# Four_Channel_Relay_Driver.net
KiCad netlist of a schematic drawn in EAGLE
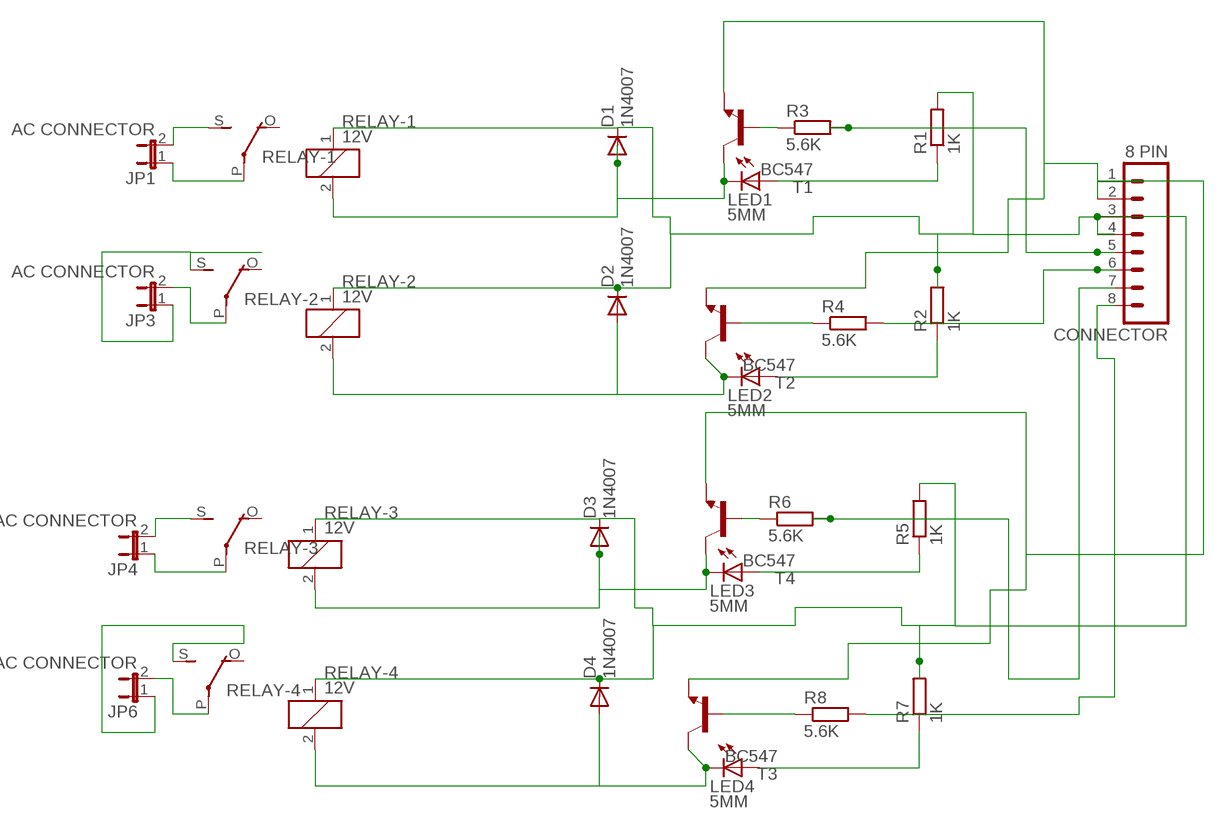
[diagram p0: schematic, sheet 1]

(export (version "E")
  (design (tool "Eeschema 10.0.6"))
  (components
    (comp (ref "CONNECTOR")
      (value "8 PIN")
      (footprint "eagle-import:08P")
      (libsource (lib "eagle-import") (part "M08"))
    )
    (comp (ref "D1")
      (value "1N4007")
      (footprint "eagle-import:DO41-10")
      (libsource (lib "eagle-import") (part "1N4004"))
    )
    (comp (ref "D2")
      (value "1N4007")
      (footprint "eagle-import:DO41-10")
      (libsource (lib "eagle-import") (part "1N4004"))
    )
    (comp (ref "D3")
      (value "1N4007")
      (footprint "eagle-import:DO41-10")
      (libsource (lib "eagle-import") (part "1N4004"))
    )
    (comp (ref "D4")
      (value "1N4007")
      (footprint "eagle-import:DO41-10")
      (libsource (lib "eagle-import") (part "1N4004"))
    )
    (comp (ref "JP1")
      (value "AC CONNECTOR")
      (footprint "eagle-import:JP1")
      (libsource (lib "eagle-import") (part "JP1E"))
    )
    (comp (ref "JP3")
      (value "AC CONNECTOR")
      (footprint "eagle-import:JP1")
      (libsource (lib "eagle-import") (part "JP1E"))
    )
    (comp (ref "JP4")
      (value "AC CONNECTOR")
      (footprint "eagle-import:JP1")
      (libsource (lib "eagle-import") (part "JP1E"))
    )
    (comp (ref "JP6")
      (value "AC CONNECTOR")
      (footprint "eagle-import:JP1")
      (libsource (lib "eagle-import") (part "JP1E"))
    )
    (comp (ref "LED1")
      (value "5MM")
      (footprint "eagle-import:LED5MM")
      (libsource (lib "eagle-import") (part "LED5MM"))
    )
    (comp (ref "LED2")
      (value "5MM")
      (footprint "eagle-import:LED5MM")
      (libsource (lib "eagle-import") (part "LED5MM"))
    )
    (comp (ref "LED3")
      (value "5MM")
      (footprint "eagle-import:LED5MM")
      (libsource (lib "eagle-import") (part "LED5MM"))
    )
    (comp (ref "LED4")
      (value "5MM")
      (footprint "eagle-import:LED5MM")
      (libsource (lib "eagle-import") (part "LED5MM"))
    )
    (comp (ref "R1")
      (value "1K")
      (footprint "eagle-import:0204_7")
      (libsource (lib "eagle-import") (part "R-EU_0204/7"))
    )
    (comp (ref "R2")
      (value "1K")
      (footprint "eagle-import:0204_7")
      (libsource (lib "eagle-import") (part "R-EU_0204/7"))
    )
    (comp (ref "R3")
      (value "5.6K")
      (footprint "eagle-import:0204_7")
      (libsource (lib "eagle-import") (part "R-EU_0204/7"))
    )
    (comp (ref "R4")
      (value "5.6K")
      (footprint "eagle-import:0204_7")
      (libsource (lib "eagle-import") (part "R-EU_0204/7"))
    )
    (comp (ref "R5")
      (value "1K")
      (footprint "eagle-import:0204_7")
      (libsource (lib "eagle-import") (part "R-EU_0204/7"))
    )
    (comp (ref "R6")
      (value "5.6K")
      (footprint "eagle-import:0204_7")
      (libsource (lib "eagle-import") (part "R-EU_0204/7"))
    )
    (comp (ref "R7")
      (value "1K")
      (footprint "eagle-import:0204_7")
      (libsource (lib "eagle-import") (part "R-EU_0204/7"))
    )
    (comp (ref "R8")
      (value "5.6K")
      (footprint "eagle-import:0204_7")
      (libsource (lib "eagle-import") (part "R-EU_0204/7"))
    )
    (comp (ref "RELAY-1")
      (value "12V")
      (footprint "eagle-import:G5LE")
      (libsource (lib "eagle-import") (part "G5L"))
    )
    (comp (ref "RELAY-2")
      (value "12V")
      (footprint "eagle-import:G5LE")
      (libsource (lib "eagle-import") (part "G5L"))
    )
    (comp (ref "RELAY-3")
      (value "12V")
      (footprint "eagle-import:G5LE")
      (libsource (lib "eagle-import") (part "G5L"))
    )
    (comp (ref "RELAY-4")
      (value "12V")
      (footprint "eagle-import:G5LE")
      (libsource (lib "eagle-import") (part "G5L"))
    )
    (comp (ref "T1")
      (value "BC547")
      (footprint "eagle-import:TO92")
      (libsource (lib "eagle-import") (part "BC547"))
    )
    (comp (ref "T2")
      (value "BC547")
      (footprint "eagle-import:TO92")
      (libsource (lib "eagle-import") (part "BC547"))
    )
    (comp (ref "T3")
      (value "BC547")
      (footprint "eagle-import:TO92")
      (libsource (lib "eagle-import") (part "BC547"))
    )
    (comp (ref "T4")
      (value "BC547")
      (footprint "eagle-import:TO92")
      (libsource (lib "eagle-import") (part "BC547"))
    )
  )
  (nets
    (net (code "1") (name "Net-(CONNECTOR-Pad3)") (class "Default")
      (node (ref "CONNECTOR") (pin "3") (pinfunction "3_3") (pintype "passive"))
      (node (ref "CONNECTOR") (pin "4") (pinfunction "4_4") (pintype "passive"))
      (node (ref "D1") (pin "C") (pinfunction "C_C") (pintype "passive"))
      (node (ref "D2") (pin "C") (pinfunction "C_C") (pintype "passive"))
      (node (ref "D3") (pin "C") (pinfunction "C_C") (pintype "passive"))
      (node (ref "D4") (pin "C") (pinfunction "C_C") (pintype "passive"))
      (node (ref "R1") (pin "2") (pinfunction "2_2") (pintype "passive"))
      (node (ref "R2") (pin "2") (pinfunction "2_2") (pintype "passive"))
      (node (ref "R5") (pin "2") (pinfunction "2_2") (pintype "passive"))
      (node (ref "R7") (pin "2") (pinfunction "2_2") (pintype "passive"))
      (node (ref "RELAY-1") (pin "1") (pinfunction "1_1") (pintype "passive"))
      (node (ref "RELAY-2") (pin "1") (pinfunction "1_1") (pintype "passive"))
      (node (ref "RELAY-3") (pin "1") (pinfunction "1_1") (pintype "passive"))
      (node (ref "RELAY-4") (pin "1") (pinfunction "1_1") (pintype "passive"))
    )
    (net (code "2") (name "Net-(CONNECTOR-Pad5)") (class "Default")
      (node (ref "CONNECTOR") (pin "5") (pinfunction "5_5") (pintype "passive"))
      (node (ref "R3") (pin "2") (pinfunction "2_2") (pintype "passive"))
    )
    (net (code "3") (name "Net-(CONNECTOR-Pad6)") (class "Default")
      (node (ref "CONNECTOR") (pin "6") (pinfunction "6_6") (pintype "passive"))
      (node (ref "R4") (pin "2") (pinfunction "2_2") (pintype "passive"))
    )
    (net (code "4") (name "Net-(CONNECTOR-Pad7)") (class "Default")
      (node (ref "CONNECTOR") (pin "7") (pinfunction "7_7") (pintype "passive"))
      (node (ref "R6") (pin "2") (pinfunction "2_2") (pintype "passive"))
    )
    (net (code "5") (name "Net-(CONNECTOR-Pad8)") (class "Default")
      (node (ref "CONNECTOR") (pin "8") (pinfunction "8_8") (pintype "passive"))
      (node (ref "R8") (pin "2") (pinfunction "2_2") (pintype "passive"))
    )
    (net (code "6") (name "Net-(JP1-Pad1)") (class "Default")
      (node (ref "JP1") (pin "1") (pinfunction "1_1") (pintype "passive"))
      (node (ref "RELAY-1") (pin "P") (pinfunction "P_P") (pintype "passive"))
    )
    (net (code "7") (name "Net-(JP1-Pad2)") (class "Default")
      (node (ref "JP1") (pin "2") (pinfunction "2_2") (pintype "passive"))
      (node (ref "RELAY-1") (pin "S") (pinfunction "S_S") (pintype "passive"))
    )
    (net (code "8") (name "Net-(JP3-Pad1)") (class "Default")
      (node (ref "JP3") (pin "1") (pinfunction "1_1") (pintype "passive"))
      (node (ref "RELAY-2") (pin "S") (pinfunction "S_S") (pintype "passive"))
    )
    (net (code "9") (name "Net-(JP3-Pad2)") (class "Default")
      (node (ref "JP3") (pin "2") (pinfunction "2_2") (pintype "passive"))
      (node (ref "RELAY-2") (pin "P") (pinfunction "P_P") (pintype "passive"))
    )
    (net (code "10") (name "Net-(JP4-Pad1)") (class "Default")
      (node (ref "JP4") (pin "1") (pinfunction "1_1") (pintype "passive"))
      (node (ref "RELAY-3") (pin "P") (pinfunction "P_P") (pintype "passive"))
    )
    (net (code "11") (name "Net-(JP4-Pad2)") (class "Default")
      (node (ref "JP4") (pin "2") (pinfunction "2_2") (pintype "passive"))
      (node (ref "RELAY-3") (pin "S") (pinfunction "S_S") (pintype "passive"))
    )
    (net (code "12") (name "Net-(JP6-Pad1)") (class "Default")
      (node (ref "JP6") (pin "1") (pinfunction "1_1") (pintype "passive"))
      (node (ref "RELAY-4") (pin "S") (pinfunction "S_S") (pintype "passive"))
    )
    (net (code "13") (name "Net-(JP6-Pad2)") (class "Default")
      (node (ref "JP6") (pin "2") (pinfunction "2_2") (pintype "passive"))
      (node (ref "RELAY-4") (pin "P") (pinfunction "P_P") (pintype "passive"))
    )
    (net (code "14") (name "Net-(LED1-C)") (class "Default")
      (node (ref "D1") (pin "A") (pinfunction "A_A") (pintype "passive"))
      (node (ref "LED1") (pin "K") (pinfunction "C_K") (pintype "passive"))
      (node (ref "RELAY-1") (pin "2") (pinfunction "2_2") (pintype "passive"))
      (node (ref "T1") (pin "3") (pinfunction "C_3") (pintype "passive"))
    )
    (net (code "15") (name "Net-(LED1-PadA)") (class "Default")
      (node (ref "LED1") (pin "A") (pinfunction "A_A") (pintype "passive"))
      (node (ref "R1") (pin "1") (pinfunction "1_1") (pintype "passive"))
    )
    (net (code "16") (name "Net-(LED2-C)") (class "Default")
      (node (ref "D2") (pin "A") (pinfunction "A_A") (pintype "passive"))
      (node (ref "LED2") (pin "K") (pinfunction "C_K") (pintype "passive"))
      (node (ref "RELAY-2") (pin "2") (pinfunction "2_2") (pintype "passive"))
      (node (ref "T2") (pin "3") (pinfunction "C_3") (pintype "passive"))
    )
    (net (code "17") (name "Net-(LED2-PadA)") (class "Default")
      (node (ref "LED2") (pin "A") (pinfunction "A_A") (pintype "passive"))
      (node (ref "R2") (pin "1") (pinfunction "1_1") (pintype "passive"))
    )
    (net (code "18") (name "Net-(LED3-C)") (class "Default")
      (node (ref "D3") (pin "A") (pinfunction "A_A") (pintype "passive"))
      (node (ref "LED3") (pin "K") (pinfunction "C_K") (pintype "passive"))
      (node (ref "RELAY-3") (pin "2") (pinfunction "2_2") (pintype "passive"))
      (node (ref "T4") (pin "3") (pinfunction "C_3") (pintype "passive"))
    )
    (net (code "19") (name "Net-(LED3-PadA)") (class "Default")
      (node (ref "LED3") (pin "A") (pinfunction "A_A") (pintype "passive"))
      (node (ref "R5") (pin "1") (pinfunction "1_1") (pintype "passive"))
    )
    (net (code "20") (name "Net-(LED4-C)") (class "Default")
      (node (ref "D4") (pin "A") (pinfunction "A_A") (pintype "passive"))
      (node (ref "LED4") (pin "K") (pinfunction "C_K") (pintype "passive"))
      (node (ref "RELAY-4") (pin "2") (pinfunction "2_2") (pintype "passive"))
      (node (ref "T3") (pin "3") (pinfunction "C_3") (pintype "passive"))
    )
    (net (code "21") (name "Net-(LED4-PadA)") (class "Default")
      (node (ref "LED4") (pin "A") (pinfunction "A_A") (pintype "passive"))
      (node (ref "R7") (pin "1") (pinfunction "1_1") (pintype "passive"))
    )
    (net (code "22") (name "Net-(T1-B)") (class "Default")
      (node (ref "R3") (pin "1") (pinfunction "1_1") (pintype "passive"))
      (node (ref "T1") (pin "2") (pinfunction "B_2") (pintype "passive"))
    )
    (net (code "23") (name "Net-(T1-E)") (class "Default")
      (node (ref "CONNECTOR") (pin "1") (pinfunction "1_1") (pintype "passive"))
      (node (ref "CONNECTOR") (pin "2") (pinfunction "2_2") (pintype "passive"))
      (node (ref "T1") (pin "1") (pinfunction "E_1") (pintype "passive"))
      (node (ref "T2") (pin "1") (pinfunction "E_1") (pintype "passive"))
      (node (ref "T3") (pin "1") (pinfunction "E_1") (pintype "passive"))
      (node (ref "T4") (pin "1") (pinfunction "E_1") (pintype "passive"))
    )
    (net (code "24") (name "Net-(T2-B)") (class "Default")
      (node (ref "R4") (pin "1") (pinfunction "1_1") (pintype "passive"))
      (node (ref "T2") (pin "2") (pinfunction "B_2") (pintype "passive"))
    )
    (net (code "25") (name "Net-(T3-B)") (class "Default")
      (node (ref "R8") (pin "1") (pinfunction "1_1") (pintype "passive"))
      (node (ref "T3") (pin "2") (pinfunction "B_2") (pintype "passive"))
    )
    (net (code "26") (name "Net-(T4-B)") (class "Default")
      (node (ref "R6") (pin "1") (pinfunction "1_1") (pintype "passive"))
      (node (ref "T4") (pin "2") (pinfunction "B_2") (pintype "passive"))
    )
    (net (code "27") (name "unconnected-(RELAY-1-PadO)") (class "Default")
      (node (ref "RELAY-1") (pin "O") (pinfunction "O_O") (pintype "passive"))
    )
    (net (code "28") (name "unconnected-(RELAY-2-PadO)") (class "Default")
      (node (ref "RELAY-2") (pin "O") (pinfunction "O_O") (pintype "passive"))
    )
    (net (code "29") (name "unconnected-(RELAY-3-PadO)") (class "Default")
      (node (ref "RELAY-3") (pin "O") (pinfunction "O_O") (pintype "passive"))
    )
    (net (code "30") (name "unconnected-(RELAY-4-PadO)") (class "Default")
      (node (ref "RELAY-4") (pin "O") (pinfunction "O_O") (pintype "passive"))
    )
  )
)
